# power.net
KiCad netlist of a schematic drawn in EAGLE
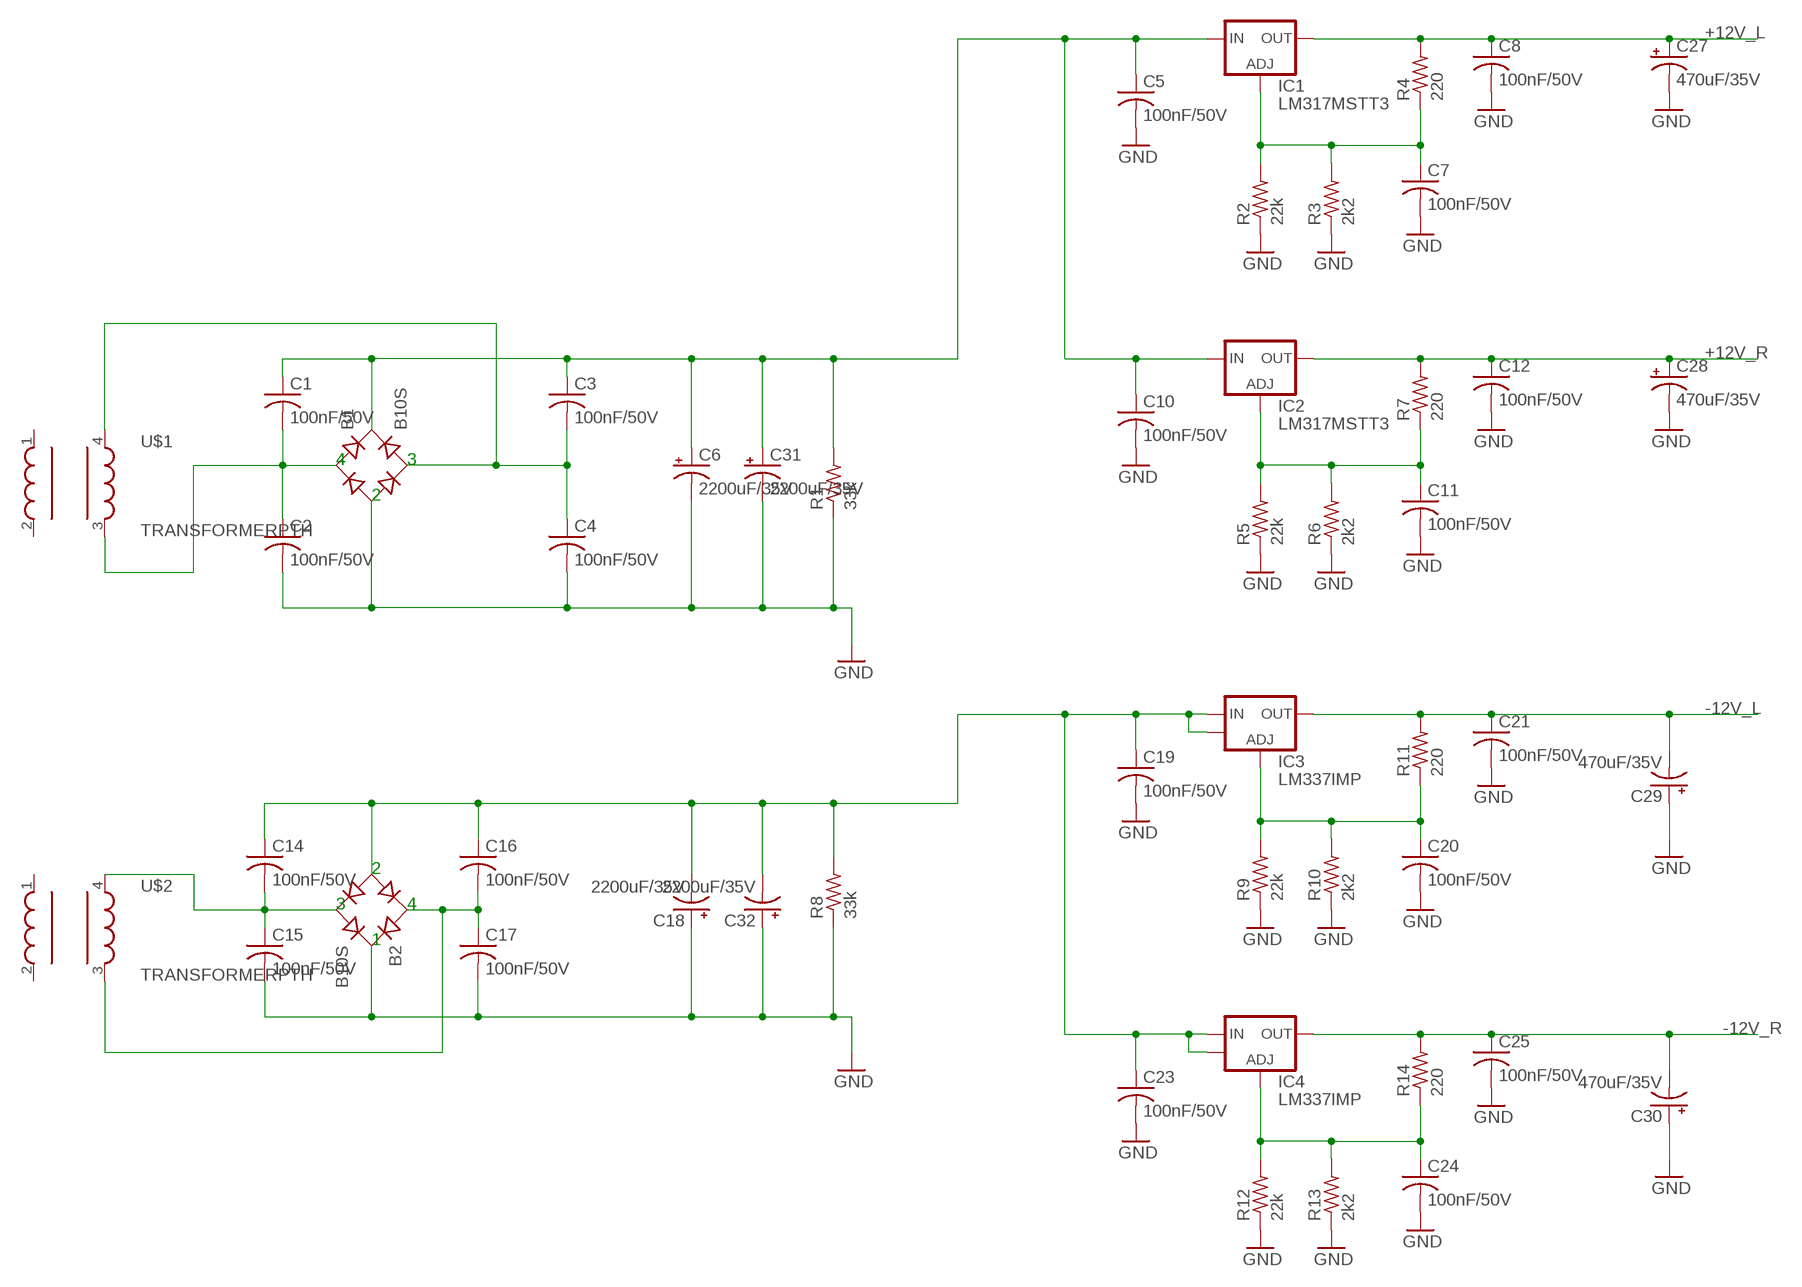
[diagram p0: schematic, sheet 1]

(export (version "E")
  (design (tool "Eeschema 10.0.6"))
  (components
    (comp (ref "B1")
      (value "B10S")
      (footprint "eagle-import:MBS")
      (libsource (lib "eagle-import") (part "BS10"))
    )
    (comp (ref "B2")
      (value "B10S")
      (footprint "eagle-import:MBS")
      (libsource (lib "eagle-import") (part "BS10"))
    )
    (comp (ref "C1")
      (value "100nF/50V")
      (footprint "eagle-import:C0805")
      (libsource (lib "eagle-import") (part "C-USC0805"))
    )
    (comp (ref "C2")
      (value "100nF/50V")
      (footprint "eagle-import:C0805")
      (libsource (lib "eagle-import") (part "C-USC0805"))
    )
    (comp (ref "C3")
      (value "100nF/50V")
      (footprint "eagle-import:C0805")
      (libsource (lib "eagle-import") (part "C-USC0805"))
    )
    (comp (ref "C4")
      (value "100nF/50V")
      (footprint "eagle-import:C0805")
      (libsource (lib "eagle-import") (part "C-USC0805"))
    )
    (comp (ref "C5")
      (value "100nF/50V")
      (footprint "eagle-import:C0805")
      (libsource (lib "eagle-import") (part "C-USC0805"))
    )
    (comp (ref "C6")
      (value "2200uF/35V")
      (footprint "eagle-import:E5-13")
      (libsource (lib "eagle-import") (part "CPOL-USE5-13"))
    )
    (comp (ref "C7")
      (value "100nF/50V")
      (footprint "eagle-import:C0805")
      (libsource (lib "eagle-import") (part "C-USC0805"))
    )
    (comp (ref "C8")
      (value "100nF/50V")
      (footprint "eagle-import:C0805")
      (libsource (lib "eagle-import") (part "C-USC0805"))
    )
    (comp (ref "C10")
      (value "100nF/50V")
      (footprint "eagle-import:C0805")
      (libsource (lib "eagle-import") (part "C-USC0805"))
    )
    (comp (ref "C11")
      (value "100nF/50V")
      (footprint "eagle-import:C0805")
      (libsource (lib "eagle-import") (part "C-USC0805"))
    )
    (comp (ref "C12")
      (value "100nF/50V")
      (footprint "eagle-import:C0805")
      (libsource (lib "eagle-import") (part "C-USC0805"))
    )
    (comp (ref "C14")
      (value "100nF/50V")
      (footprint "eagle-import:C0805")
      (libsource (lib "eagle-import") (part "C-USC0805"))
    )
    (comp (ref "C15")
      (value "100nF/50V")
      (footprint "eagle-import:C0805")
      (libsource (lib "eagle-import") (part "C-USC0805"))
    )
    (comp (ref "C16")
      (value "100nF/50V")
      (footprint "eagle-import:C0805")
      (libsource (lib "eagle-import") (part "C-USC0805"))
    )
    (comp (ref "C17")
      (value "100nF/50V")
      (footprint "eagle-import:C0805")
      (libsource (lib "eagle-import") (part "C-USC0805"))
    )
    (comp (ref "C18")
      (value "2200uF/35V")
      (footprint "eagle-import:E5-13")
      (libsource (lib "eagle-import") (part "CPOL-USE5-13"))
    )
    (comp (ref "C19")
      (value "100nF/50V")
      (footprint "eagle-import:C0805")
      (libsource (lib "eagle-import") (part "C-USC0805"))
    )
    (comp (ref "C20")
      (value "100nF/50V")
      (footprint "eagle-import:C0805")
      (libsource (lib "eagle-import") (part "C-USC0805"))
    )
    (comp (ref "C21")
      (value "100nF/50V")
      (footprint "eagle-import:C0805")
      (libsource (lib "eagle-import") (part "C-USC0805"))
    )
    (comp (ref "C23")
      (value "100nF/50V")
      (footprint "eagle-import:C0805")
      (libsource (lib "eagle-import") (part "C-USC0805"))
    )
    (comp (ref "C24")
      (value "100nF/50V")
      (footprint "eagle-import:C0805")
      (libsource (lib "eagle-import") (part "C-USC0805"))
    )
    (comp (ref "C25")
      (value "100nF/50V")
      (footprint "eagle-import:C0805")
      (libsource (lib "eagle-import") (part "C-USC0805"))
    )
    (comp (ref "C27")
      (value "470uF/35V")
      (footprint "eagle-import:E5-13")
      (libsource (lib "eagle-import") (part "CPOL-USE5-13"))
    )
    (comp (ref "C28")
      (value "470uF/35V")
      (footprint "eagle-import:E5-13")
      (libsource (lib "eagle-import") (part "CPOL-USE5-13"))
    )
    (comp (ref "C29")
      (value "470uF/35V")
      (footprint "eagle-import:E5-13")
      (libsource (lib "eagle-import") (part "CPOL-USE5-13"))
    )
    (comp (ref "C30")
      (value "470uF/35V")
      (footprint "eagle-import:E5-13")
      (libsource (lib "eagle-import") (part "CPOL-USE5-13"))
    )
    (comp (ref "C31")
      (value "2200uF/35V")
      (footprint "eagle-import:E5-13")
      (libsource (lib "eagle-import") (part "CPOL-USE5-13"))
    )
    (comp (ref "C32")
      (value "2200uF/35V")
      (footprint "eagle-import:E5-13")
      (libsource (lib "eagle-import") (part "CPOL-USE5-13"))
    )
    (comp (ref "IC1")
      (value "LM317MSTT3")
      (footprint "eagle-import:SOT223")
      (libsource (lib "eagle-import") (part "LM317?MSTT3"))
    )
    (comp (ref "IC2")
      (value "LM317MSTT3")
      (footprint "eagle-import:SOT223")
      (libsource (lib "eagle-import") (part "LM317?MSTT3"))
    )
    (comp (ref "IC3")
      (value "LM337IMP")
      (footprint "eagle-import:SOT-223")
      (libsource (lib "eagle-import") (part "LM337IMP"))
    )
    (comp (ref "IC4")
      (value "LM337IMP")
      (footprint "eagle-import:SOT-223")
      (libsource (lib "eagle-import") (part "LM337IMP"))
    )
    (comp (ref "R1")
      (value "33k")
      (footprint "eagle-import:M0805")
      (libsource (lib "eagle-import") (part "R-US_M0805"))
    )
    (comp (ref "R2")
      (value "22k")
      (footprint "eagle-import:M0805")
      (libsource (lib "eagle-import") (part "R-US_M0805"))
    )
    (comp (ref "R3")
      (value "2k2")
      (footprint "eagle-import:M0805")
      (libsource (lib "eagle-import") (part "R-US_M0805"))
    )
    (comp (ref "R4")
      (value "220")
      (footprint "eagle-import:M0805")
      (libsource (lib "eagle-import") (part "R-US_M0805"))
    )
    (comp (ref "R5")
      (value "22k")
      (footprint "eagle-import:M0805")
      (libsource (lib "eagle-import") (part "R-US_M0805"))
    )
    (comp (ref "R6")
      (value "2k2")
      (footprint "eagle-import:M0805")
      (libsource (lib "eagle-import") (part "R-US_M0805"))
    )
    (comp (ref "R7")
      (value "220")
      (footprint "eagle-import:M0805")
      (libsource (lib "eagle-import") (part "R-US_M0805"))
    )
    (comp (ref "R8")
      (value "33k")
      (footprint "eagle-import:M0805")
      (libsource (lib "eagle-import") (part "R-US_M0805"))
    )
    (comp (ref "R9")
      (value "22k")
      (footprint "eagle-import:M0805")
      (libsource (lib "eagle-import") (part "R-US_M0805"))
    )
    (comp (ref "R10")
      (value "2k2")
      (footprint "eagle-import:M0805")
      (libsource (lib "eagle-import") (part "R-US_M0805"))
    )
    (comp (ref "R11")
      (value "220")
      (footprint "eagle-import:M0805")
      (libsource (lib "eagle-import") (part "R-US_M0805"))
    )
    (comp (ref "R12")
      (value "22k")
      (footprint "eagle-import:M0805")
      (libsource (lib "eagle-import") (part "R-US_M0805"))
    )
    (comp (ref "R13")
      (value "2k2")
      (footprint "eagle-import:M0805")
      (libsource (lib "eagle-import") (part "R-US_M0805"))
    )
    (comp (ref "R14")
      (value "220")
      (footprint "eagle-import:M0805")
      (libsource (lib "eagle-import") (part "R-US_M0805"))
    )
    (comp (ref "U$1")
      (value "TRANSFORMERPTH")
      (footprint "eagle-import:TRANSFORMER")
      (libsource (lib "eagle-import") (part "TRANSFORMERPTH"))
    )
    (comp (ref "U$2")
      (value "TRANSFORMERPTH")
      (footprint "eagle-import:TRANSFORMER")
      (libsource (lib "eagle-import") (part "TRANSFORMERPTH"))
    )
  )
  (nets
    (net (code "1") (name "/+12V_L") (class "Default")
      (node (ref "C27") (pin "+") (pinfunction "+_+") (pintype "passive"))
      (node (ref "C8") (pin "1") (pinfunction "1_1") (pintype "passive"))
      (node (ref "IC1") (pin "4") (pinfunction "OUT_4") (pintype "passive"))
      (node (ref "R4") (pin "2") (pinfunction "2_2") (pintype "passive"))
    )
    (net (code "2") (name "/+12V_R") (class "Default")
      (node (ref "C12") (pin "1") (pinfunction "1_1") (pintype "passive"))
      (node (ref "C28") (pin "+") (pinfunction "+_+") (pintype "passive"))
      (node (ref "IC2") (pin "4") (pinfunction "OUT_4") (pintype "passive"))
      (node (ref "R7") (pin "2") (pinfunction "2_2") (pintype "passive"))
    )
    (net (code "3") (name "/-12V_L") (class "Default")
      (node (ref "C21") (pin "1") (pinfunction "1_1") (pintype "passive"))
      (node (ref "C29") (pin "-") (pinfunction "-_-") (pintype "passive"))
      (node (ref "IC3") (pin "3") (pinfunction "OUT_3") (pintype "passive"))
      (node (ref "R11") (pin "2") (pinfunction "2_2") (pintype "passive"))
    )
    (net (code "4") (name "/-12V_R") (class "Default")
      (node (ref "C25") (pin "1") (pinfunction "1_1") (pintype "passive"))
      (node (ref "C30") (pin "-") (pinfunction "-_-") (pintype "passive"))
      (node (ref "IC4") (pin "3") (pinfunction "OUT_3") (pintype "passive"))
      (node (ref "R14") (pin "2") (pinfunction "2_2") (pintype "passive"))
    )
    (net (code "5") (name "GND") (class "Default")
      (node (ref "B1") (pin "-") (pinfunction "-_-") (pintype "passive"))
      (node (ref "B2") (pin "+") (pinfunction "+_+") (pintype "passive"))
      (node (ref "C10") (pin "2") (pinfunction "2_2") (pintype "passive"))
      (node (ref "C11") (pin "2") (pinfunction "2_2") (pintype "passive"))
      (node (ref "C12") (pin "2") (pinfunction "2_2") (pintype "passive"))
      (node (ref "C15") (pin "2") (pinfunction "2_2") (pintype "passive"))
      (node (ref "C17") (pin "2") (pinfunction "2_2") (pintype "passive"))
      (node (ref "C18") (pin "+") (pinfunction "+_+") (pintype "passive"))
      (node (ref "C19") (pin "2") (pinfunction "2_2") (pintype "passive"))
      (node (ref "C2") (pin "2") (pinfunction "2_2") (pintype "passive"))
      (node (ref "C20") (pin "2") (pinfunction "2_2") (pintype "passive"))
      (node (ref "C21") (pin "2") (pinfunction "2_2") (pintype "passive"))
      (node (ref "C23") (pin "2") (pinfunction "2_2") (pintype "passive"))
      (node (ref "C24") (pin "2") (pinfunction "2_2") (pintype "passive"))
      (node (ref "C25") (pin "2") (pinfunction "2_2") (pintype "passive"))
      (node (ref "C27") (pin "-") (pinfunction "-_-") (pintype "passive"))
      (node (ref "C28") (pin "-") (pinfunction "-_-") (pintype "passive"))
      (node (ref "C29") (pin "+") (pinfunction "+_+") (pintype "passive"))
      (node (ref "C30") (pin "+") (pinfunction "+_+") (pintype "passive"))
      (node (ref "C31") (pin "-") (pinfunction "-_-") (pintype "passive"))
      (node (ref "C32") (pin "+") (pinfunction "+_+") (pintype "passive"))
      (node (ref "C4") (pin "2") (pinfunction "2_2") (pintype "passive"))
      (node (ref "C5") (pin "2") (pinfunction "2_2") (pintype "passive"))
      (node (ref "C6") (pin "-") (pinfunction "-_-") (pintype "passive"))
      (node (ref "C7") (pin "2") (pinfunction "2_2") (pintype "passive"))
      (node (ref "C8") (pin "2") (pinfunction "2_2") (pintype "passive"))
      (node (ref "R1") (pin "1") (pinfunction "1_1") (pintype "passive"))
      (node (ref "R10") (pin "1") (pinfunction "1_1") (pintype "passive"))
      (node (ref "R12") (pin "1") (pinfunction "1_1") (pintype "passive"))
      (node (ref "R13") (pin "1") (pinfunction "1_1") (pintype "passive"))
      (node (ref "R2") (pin "1") (pinfunction "1_1") (pintype "passive"))
      (node (ref "R3") (pin "1") (pinfunction "1_1") (pintype "passive"))
      (node (ref "R5") (pin "1") (pinfunction "1_1") (pintype "passive"))
      (node (ref "R6") (pin "1") (pinfunction "1_1") (pintype "passive"))
      (node (ref "R8") (pin "1") (pinfunction "1_1") (pintype "passive"))
      (node (ref "R9") (pin "1") (pinfunction "1_1") (pintype "passive"))
    )
    (net (code "6") (name "Net-(B1-PadAC1)") (class "Default")
      (node (ref "B1") (pin "AC1") (pinfunction "AC1_AC1") (pintype "passive"))
      (node (ref "C1") (pin "2") (pinfunction "2_2") (pintype "passive"))
      (node (ref "C2") (pin "1") (pinfunction "1_1") (pintype "passive"))
      (node (ref "U$1") (pin "3") (pinfunction "3_3") (pintype "bidirectional"))
    )
    (net (code "7") (name "Net-(B1-PadAC2)") (class "Default")
      (node (ref "B1") (pin "AC2") (pinfunction "AC2_AC2") (pintype "passive"))
      (node (ref "C3") (pin "2") (pinfunction "2_2") (pintype "passive"))
      (node (ref "C4") (pin "1") (pinfunction "1_1") (pintype "passive"))
      (node (ref "U$1") (pin "4") (pinfunction "4_4") (pintype "bidirectional"))
    )
    (net (code "8") (name "Net-(B2-PadAC1)") (class "Default")
      (node (ref "B2") (pin "AC1") (pinfunction "AC1_AC1") (pintype "passive"))
      (node (ref "C16") (pin "2") (pinfunction "2_2") (pintype "passive"))
      (node (ref "C17") (pin "1") (pinfunction "1_1") (pintype "passive"))
      (node (ref "U$2") (pin "3") (pinfunction "3_3") (pintype "bidirectional"))
    )
    (net (code "9") (name "Net-(B2-PadAC2)") (class "Default")
      (node (ref "B2") (pin "AC2") (pinfunction "AC2_AC2") (pintype "passive"))
      (node (ref "C14") (pin "2") (pinfunction "2_2") (pintype "passive"))
      (node (ref "C15") (pin "1") (pinfunction "1_1") (pintype "passive"))
      (node (ref "U$2") (pin "4") (pinfunction "4_4") (pintype "bidirectional"))
    )
    (net (code "10") (name "Net-(IC1-ADJ)") (class "Default")
      (node (ref "C7") (pin "1") (pinfunction "1_1") (pintype "passive"))
      (node (ref "IC1") (pin "1") (pinfunction "ADJ_1") (pintype "input"))
      (node (ref "R2") (pin "2") (pinfunction "2_2") (pintype "passive"))
      (node (ref "R3") (pin "2") (pinfunction "2_2") (pintype "passive"))
      (node (ref "R4") (pin "1") (pinfunction "1_1") (pintype "passive"))
    )
    (net (code "11") (name "Net-(IC1-IN)") (class "Default")
      (node (ref "B1") (pin "+") (pinfunction "+_+") (pintype "passive"))
      (node (ref "C1") (pin "1") (pinfunction "1_1") (pintype "passive"))
      (node (ref "C10") (pin "1") (pinfunction "1_1") (pintype "passive"))
      (node (ref "C3") (pin "1") (pinfunction "1_1") (pintype "passive"))
      (node (ref "C31") (pin "+") (pinfunction "+_+") (pintype "passive"))
      (node (ref "C5") (pin "1") (pinfunction "1_1") (pintype "passive"))
      (node (ref "C6") (pin "+") (pinfunction "+_+") (pintype "passive"))
      (node (ref "IC1") (pin "3") (pinfunction "IN_3") (pintype "input"))
      (node (ref "IC2") (pin "3") (pinfunction "IN_3") (pintype "input"))
      (node (ref "R1") (pin "2") (pinfunction "2_2") (pintype "passive"))
    )
    (net (code "12") (name "Net-(IC2-ADJ)") (class "Default")
      (node (ref "C11") (pin "1") (pinfunction "1_1") (pintype "passive"))
      (node (ref "IC2") (pin "1") (pinfunction "ADJ_1") (pintype "input"))
      (node (ref "R5") (pin "2") (pinfunction "2_2") (pintype "passive"))
      (node (ref "R6") (pin "2") (pinfunction "2_2") (pintype "passive"))
      (node (ref "R7") (pin "1") (pinfunction "1_1") (pintype "passive"))
    )
    (net (code "13") (name "Net-(IC3-ADJ)") (class "Default")
      (node (ref "C20") (pin "1") (pinfunction "1_1") (pintype "passive"))
      (node (ref "IC3") (pin "1") (pinfunction "ADJ_1") (pintype "input"))
      (node (ref "R10") (pin "2") (pinfunction "2_2") (pintype "passive"))
      (node (ref "R11") (pin "1") (pinfunction "1_1") (pintype "passive"))
      (node (ref "R9") (pin "2") (pinfunction "2_2") (pintype "passive"))
    )
    (net (code "14") (name "Net-(IC3-IN)") (class "Default")
      (node (ref "B2") (pin "-") (pinfunction "-_-") (pintype "passive"))
      (node (ref "C14") (pin "1") (pinfunction "1_1") (pintype "passive"))
      (node (ref "C16") (pin "1") (pinfunction "1_1") (pintype "passive"))
      (node (ref "C18") (pin "-") (pinfunction "-_-") (pintype "passive"))
      (node (ref "C19") (pin "1") (pinfunction "1_1") (pintype "passive"))
      (node (ref "C23") (pin "1") (pinfunction "1_1") (pintype "passive"))
      (node (ref "C32") (pin "-") (pinfunction "-_-") (pintype "passive"))
      (node (ref "IC3") (pin "2") (pinfunction "IN_2") (pintype "input"))
      (node (ref "IC3") (pin "4") (pinfunction "P$1_4") (pintype "bidirectional"))
      (node (ref "IC4") (pin "2") (pinfunction "IN_2") (pintype "input"))
      (node (ref "IC4") (pin "4") (pinfunction "P$1_4") (pintype "bidirectional"))
      (node (ref "R8") (pin "2") (pinfunction "2_2") (pintype "passive"))
    )
    (net (code "15") (name "Net-(IC4-ADJ)") (class "Default")
      (node (ref "C24") (pin "1") (pinfunction "1_1") (pintype "passive"))
      (node (ref "IC4") (pin "1") (pinfunction "ADJ_1") (pintype "input"))
      (node (ref "R12") (pin "2") (pinfunction "2_2") (pintype "passive"))
      (node (ref "R13") (pin "2") (pinfunction "2_2") (pintype "passive"))
      (node (ref "R14") (pin "1") (pinfunction "1_1") (pintype "passive"))
    )
    (net (code "16") (name "unconnected-(U$1-Pad1)") (class "Default")
      (node (ref "U$1") (pin "1") (pinfunction "1_1") (pintype "bidirectional"))
    )
    (net (code "17") (name "unconnected-(U$1-Pad2)") (class "Default")
      (node (ref "U$1") (pin "2") (pinfunction "2_2") (pintype "bidirectional"))
    )
    (net (code "18") (name "unconnected-(U$2-Pad1)") (class "Default")
      (node (ref "U$2") (pin "1") (pinfunction "1_1") (pintype "bidirectional"))
    )
    (net (code "19") (name "unconnected-(U$2-Pad2)") (class "Default")
      (node (ref "U$2") (pin "2") (pinfunction "2_2") (pintype "bidirectional"))
    )
  )
)
